# bone_capes.net
KiCad netlist of a schematic drawn in Altium Designer
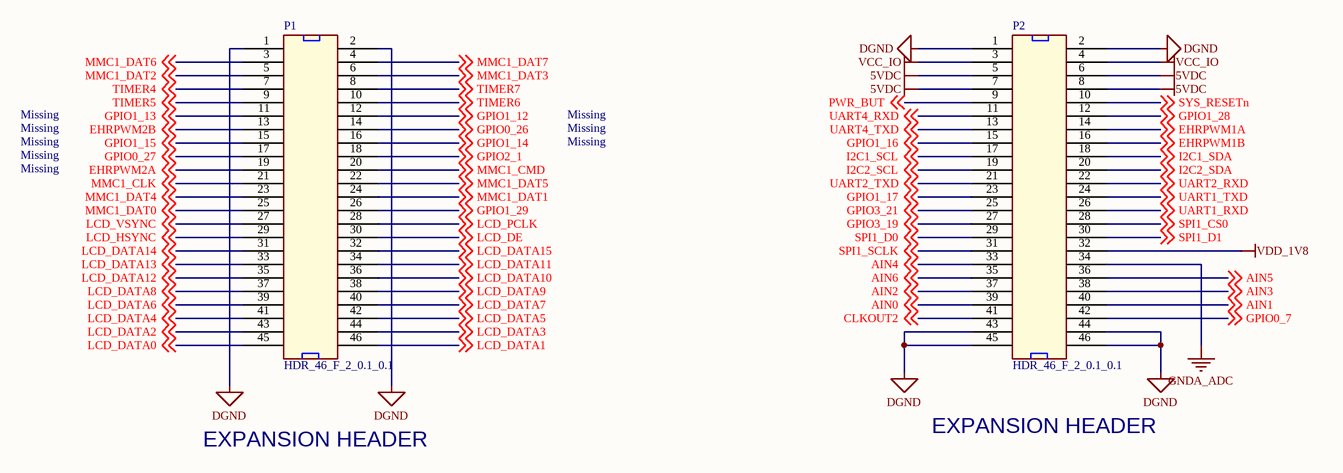
[diagram p0: bone_capes.SchDoc]

(export (version "E")
  (design (tool "Eeschema 10.0.6"))
  (components
    (comp (ref "P1")
      (value "HDR_46_F_2_0.1_0.1")
      (footprint "DIP46")
      (description "NN HEADER FMAL 46PS.1\" DL GOLD")
      (fields (field (name "MFR") "major league electronics"))
      (libsource (lib "am335x-base") (part "HDR_46_F_2_0.1_0.1"))
    )
    (comp (ref "P2")
      (value "HDR_46_F_2_0.1_0.1")
      (footprint "DIP46")
      (description "NN HEADER FMAL 46PS.1\" DL GOLD")
      (fields (field (name "MFR") "major league electronics"))
      (libsource (lib "am335x-base") (part "HDR_46_F_2_0.1_0.1"))
    )
  )
  (nets
    (net (code "1") (name "5VDC") (class "Default")
      (node (ref "P2") (pin "5") (pinfunction "3_5") (pintype "passive"))
      (node (ref "P2") (pin "6") (pinfunction "28_6") (pintype "passive"))
      (node (ref "P2") (pin "7") (pinfunction "4_7") (pintype "passive"))
      (node (ref "P2") (pin "8") (pinfunction "29_8") (pintype "passive"))
    )
    (net (code "2") (name "AIN0") (class "Default")
      (node (ref "P2") (pin "39") (pinfunction "20_39") (pintype "passive"))
    )
    (net (code "3") (name "AIN1") (class "Default")
      (node (ref "P2") (pin "40") (pinfunction "45_40") (pintype "passive"))
    )
    (net (code "4") (name "AIN2") (class "Default")
      (node (ref "P2") (pin "37") (pinfunction "19_37") (pintype "passive"))
    )
    (net (code "5") (name "AIN3") (class "Default")
      (node (ref "P2") (pin "38") (pinfunction "44_38") (pintype "passive"))
    )
    (net (code "6") (name "AIN4") (class "Default")
      (node (ref "P2") (pin "33") (pinfunction "17_33") (pintype "passive"))
    )
    (net (code "7") (name "AIN5") (class "Default")
      (node (ref "P2") (pin "36") (pinfunction "43_36") (pintype "passive"))
    )
    (net (code "8") (name "AIN6") (class "Default")
      (node (ref "P2") (pin "35") (pinfunction "18_35") (pintype "passive"))
    )
    (net (code "9") (name "CLKOUT2") (class "Default")
      (node (ref "P2") (pin "41") (pinfunction "21_41") (pintype "passive"))
    )
    (net (code "10") (name "DGND") (class "Default")
      (node (ref "P1") (pin "1") (pinfunction "1_1") (pintype "passive"))
      (node (ref "P1") (pin "2") (pinfunction "26_2") (pintype "passive"))
      (node (ref "P2") (pin "1") (pinfunction "1_1") (pintype "passive"))
      (node (ref "P2") (pin "2") (pinfunction "26_2") (pintype "passive"))
      (node (ref "P2") (pin "43") (pinfunction "22_43") (pintype "passive"))
      (node (ref "P2") (pin "44") (pinfunction "47_44") (pintype "passive"))
      (node (ref "P2") (pin "45") (pinfunction "23_45") (pintype "passive"))
      (node (ref "P2") (pin "46") (pinfunction "48_46") (pintype "passive"))
    )
    (net (code "11") (name "EHRPWM1A") (class "Default")
      (node (ref "P2") (pin "14") (pinfunction "32_14") (pintype "passive"))
    )
    (net (code "12") (name "EHRPWM1B") (class "Default")
      (node (ref "P2") (pin "16") (pinfunction "33_16") (pintype "passive"))
    )
    (net (code "13") (name "EHRPWM2A") (class "Default")
      (node (ref "P1") (pin "19") (pinfunction "10_19") (pintype "passive"))
    )
    (net (code "14") (name "EHRPWM2B") (class "Default")
      (node (ref "P1") (pin "13") (pinfunction "7_13") (pintype "passive"))
    )
    (net (code "15") (name "GNDA_ADC") (class "Default")
      (node (ref "P2") (pin "34") (pinfunction "42_34") (pintype "passive"))
    )
    (net (code "16") (name "GPIO0_7") (class "Default")
      (node (ref "P2") (pin "42") (pinfunction "46_42") (pintype "passive"))
    )
    (net (code "17") (name "GPIO0_26") (class "Default")
      (node (ref "P1") (pin "14") (pinfunction "32_14") (pintype "passive"))
    )
    (net (code "18") (name "GPIO0_27") (class "Default")
      (node (ref "P1") (pin "17") (pinfunction "9_17") (pintype "passive"))
    )
    (net (code "19") (name "GPIO1_12") (class "Default")
      (node (ref "P1") (pin "12") (pinfunction "31_12") (pintype "passive"))
    )
    (net (code "20") (name "GPIO1_13") (class "Default")
      (node (ref "P1") (pin "11") (pinfunction "6_11") (pintype "passive"))
    )
    (net (code "21") (name "GPIO1_14") (class "Default")
      (node (ref "P1") (pin "16") (pinfunction "33_16") (pintype "passive"))
    )
    (net (code "22") (name "GPIO1_15") (class "Default")
      (node (ref "P1") (pin "15") (pinfunction "8_15") (pintype "passive"))
    )
    (net (code "23") (name "GPIO1_16") (class "Default")
      (node (ref "P2") (pin "15") (pinfunction "8_15") (pintype "passive"))
    )
    (net (code "24") (name "GPIO1_17") (class "Default")
      (node (ref "P2") (pin "23") (pinfunction "12_23") (pintype "passive"))
    )
    (net (code "25") (name "GPIO1_28") (class "Default")
      (node (ref "P2") (pin "12") (pinfunction "31_12") (pintype "passive"))
    )
    (net (code "26") (name "GPIO1_29") (class "Default")
      (node (ref "P1") (pin "26") (pinfunction "38_26") (pintype "passive"))
    )
    (net (code "27") (name "GPIO2_1") (class "Default")
      (node (ref "P1") (pin "18") (pinfunction "34_18") (pintype "passive"))
    )
    (net (code "28") (name "GPIO3_19") (class "Default")
      (node (ref "P2") (pin "27") (pinfunction "14_27") (pintype "passive"))
    )
    (net (code "29") (name "GPIO3_21") (class "Default")
      (node (ref "P2") (pin "25") (pinfunction "13_25") (pintype "passive"))
    )
    (net (code "30") (name "I2C1_SCL") (class "Default")
      (node (ref "P2") (pin "17") (pinfunction "9_17") (pintype "passive"))
    )
    (net (code "31") (name "I2C1_SDA") (class "Default")
      (node (ref "P2") (pin "18") (pinfunction "34_18") (pintype "passive"))
    )
    (net (code "32") (name "I2C2_SCL") (class "Default")
      (node (ref "P2") (pin "19") (pinfunction "10_19") (pintype "passive"))
    )
    (net (code "33") (name "I2C2_SDA") (class "Default")
      (node (ref "P2") (pin "20") (pinfunction "35_20") (pintype "passive"))
    )
    (net (code "34") (name "LCD_DATA0") (class "Default")
      (node (ref "P1") (pin "45") (pinfunction "23_45") (pintype "passive"))
    )
    (net (code "35") (name "LCD_DATA1") (class "Default")
      (node (ref "P1") (pin "46") (pinfunction "48_46") (pintype "passive"))
    )
    (net (code "36") (name "LCD_DATA2") (class "Default")
      (node (ref "P1") (pin "43") (pinfunction "22_43") (pintype "passive"))
    )
    (net (code "37") (name "LCD_DATA3") (class "Default")
      (node (ref "P1") (pin "44") (pinfunction "47_44") (pintype "passive"))
    )
    (net (code "38") (name "LCD_DATA4") (class "Default")
      (node (ref "P1") (pin "41") (pinfunction "21_41") (pintype "passive"))
    )
    (net (code "39") (name "LCD_DATA5") (class "Default")
      (node (ref "P1") (pin "42") (pinfunction "46_42") (pintype "passive"))
    )
    (net (code "40") (name "LCD_DATA6") (class "Default")
      (node (ref "P1") (pin "39") (pinfunction "20_39") (pintype "passive"))
    )
    (net (code "41") (name "LCD_DATA7") (class "Default")
      (node (ref "P1") (pin "40") (pinfunction "45_40") (pintype "passive"))
    )
    (net (code "42") (name "LCD_DATA8") (class "Default")
      (node (ref "P1") (pin "37") (pinfunction "19_37") (pintype "passive"))
    )
    (net (code "43") (name "LCD_DATA9") (class "Default")
      (node (ref "P1") (pin "38") (pinfunction "44_38") (pintype "passive"))
    )
    (net (code "44") (name "LCD_DATA10") (class "Default")
      (node (ref "P1") (pin "36") (pinfunction "43_36") (pintype "passive"))
    )
    (net (code "45") (name "LCD_DATA11") (class "Default")
      (node (ref "P1") (pin "34") (pinfunction "42_34") (pintype "passive"))
    )
    (net (code "46") (name "LCD_DATA12") (class "Default")
      (node (ref "P1") (pin "35") (pinfunction "18_35") (pintype "passive"))
    )
    (net (code "47") (name "LCD_DATA13") (class "Default")
      (node (ref "P1") (pin "33") (pinfunction "17_33") (pintype "passive"))
    )
    (net (code "48") (name "LCD_DATA14") (class "Default")
      (node (ref "P1") (pin "31") (pinfunction "16_31") (pintype "passive"))
    )
    (net (code "49") (name "LCD_DATA15") (class "Default")
      (node (ref "P1") (pin "32") (pinfunction "41_32") (pintype "passive"))
    )
    (net (code "50") (name "LCD_DE") (class "Default")
      (node (ref "P1") (pin "30") (pinfunction "40_30") (pintype "passive"))
    )
    (net (code "51") (name "LCD_HSYNC") (class "Default")
      (node (ref "P1") (pin "29") (pinfunction "15_29") (pintype "passive"))
    )
    (net (code "52") (name "LCD_PCLK") (class "Default")
      (node (ref "P1") (pin "28") (pinfunction "39_28") (pintype "passive"))
    )
    (net (code "53") (name "LCD_VSYNC") (class "Default")
      (node (ref "P1") (pin "27") (pinfunction "14_27") (pintype "passive"))
    )
    (net (code "54") (name "MMC1_CLK") (class "Default")
      (node (ref "P1") (pin "21") (pinfunction "11_21") (pintype "passive"))
    )
    (net (code "55") (name "MMC1_CMD") (class "Default")
      (node (ref "P1") (pin "20") (pinfunction "35_20") (pintype "passive"))
    )
    (net (code "56") (name "MMC1_DAT0") (class "Default")
      (node (ref "P1") (pin "25") (pinfunction "13_25") (pintype "passive"))
    )
    (net (code "57") (name "MMC1_DAT1") (class "Default")
      (node (ref "P1") (pin "24") (pinfunction "37_24") (pintype "passive"))
    )
    (net (code "58") (name "MMC1_DAT2") (class "Default")
      (node (ref "P1") (pin "5") (pinfunction "3_5") (pintype "passive"))
    )
    (net (code "59") (name "MMC1_DAT3") (class "Default")
      (node (ref "P1") (pin "6") (pinfunction "28_6") (pintype "passive"))
    )
    (net (code "60") (name "MMC1_DAT4") (class "Default")
      (node (ref "P1") (pin "23") (pinfunction "12_23") (pintype "passive"))
    )
    (net (code "61") (name "MMC1_DAT5") (class "Default")
      (node (ref "P1") (pin "22") (pinfunction "36_22") (pintype "passive"))
    )
    (net (code "62") (name "MMC1_DAT6") (class "Default")
      (node (ref "P1") (pin "3") (pinfunction "2_3") (pintype "passive"))
    )
    (net (code "63") (name "MMC1_DAT7") (class "Default")
      (node (ref "P1") (pin "4") (pinfunction "27_4") (pintype "passive"))
    )
    (net (code "64") (name "PWR_BUT") (class "Default")
      (node (ref "P2") (pin "9") (pinfunction "5_9") (pintype "passive"))
    )
    (net (code "65") (name "SPI1_CS0") (class "Default")
      (node (ref "P2") (pin "28") (pinfunction "39_28") (pintype "passive"))
    )
    (net (code "66") (name "SPI1_D0") (class "Default")
      (node (ref "P2") (pin "29") (pinfunction "15_29") (pintype "passive"))
    )
    (net (code "67") (name "SPI1_D1") (class "Default")
      (node (ref "P2") (pin "30") (pinfunction "40_30") (pintype "passive"))
    )
    (net (code "68") (name "SPI1_SCLK") (class "Default")
      (node (ref "P2") (pin "31") (pinfunction "16_31") (pintype "passive"))
    )
    (net (code "69") (name "SYS_RESETn") (class "Default")
      (node (ref "P2") (pin "10") (pinfunction "30_10") (pintype "passive"))
    )
    (net (code "70") (name "TIMER4") (class "Default")
      (node (ref "P1") (pin "7") (pinfunction "4_7") (pintype "passive"))
    )
    (net (code "71") (name "TIMER5") (class "Default")
      (node (ref "P1") (pin "9") (pinfunction "5_9") (pintype "passive"))
    )
    (net (code "72") (name "TIMER6") (class "Default")
      (node (ref "P1") (pin "10") (pinfunction "30_10") (pintype "passive"))
    )
    (net (code "73") (name "TIMER7") (class "Default")
      (node (ref "P1") (pin "8") (pinfunction "29_8") (pintype "passive"))
    )
    (net (code "74") (name "UART1_RXD") (class "Default")
      (node (ref "P2") (pin "26") (pinfunction "38_26") (pintype "passive"))
    )
    (net (code "75") (name "UART1_TXD") (class "Default")
      (node (ref "P2") (pin "24") (pinfunction "37_24") (pintype "passive"))
    )
    (net (code "76") (name "UART2_RXD") (class "Default")
      (node (ref "P2") (pin "22") (pinfunction "36_22") (pintype "passive"))
    )
    (net (code "77") (name "UART2_TXD") (class "Default")
      (node (ref "P2") (pin "21") (pinfunction "11_21") (pintype "passive"))
    )
    (net (code "78") (name "UART4_RXD") (class "Default")
      (node (ref "P2") (pin "11") (pinfunction "6_11") (pintype "passive"))
    )
    (net (code "79") (name "UART4_TXD") (class "Default")
      (node (ref "P2") (pin "13") (pinfunction "7_13") (pintype "passive"))
    )
    (net (code "80") (name "VCC_IO") (class "Default")
      (node (ref "P2") (pin "3") (pinfunction "2_3") (pintype "passive"))
      (node (ref "P2") (pin "4") (pinfunction "27_4") (pintype "passive"))
    )
    (net (code "81") (name "VDD_1V8") (class "Default")
      (node (ref "P2") (pin "32") (pinfunction "41_32") (pintype "passive"))
    )
  )
)
